# Volterra_Carriage_Board.net
KiCad netlist of a schematic drawn in EAGLE
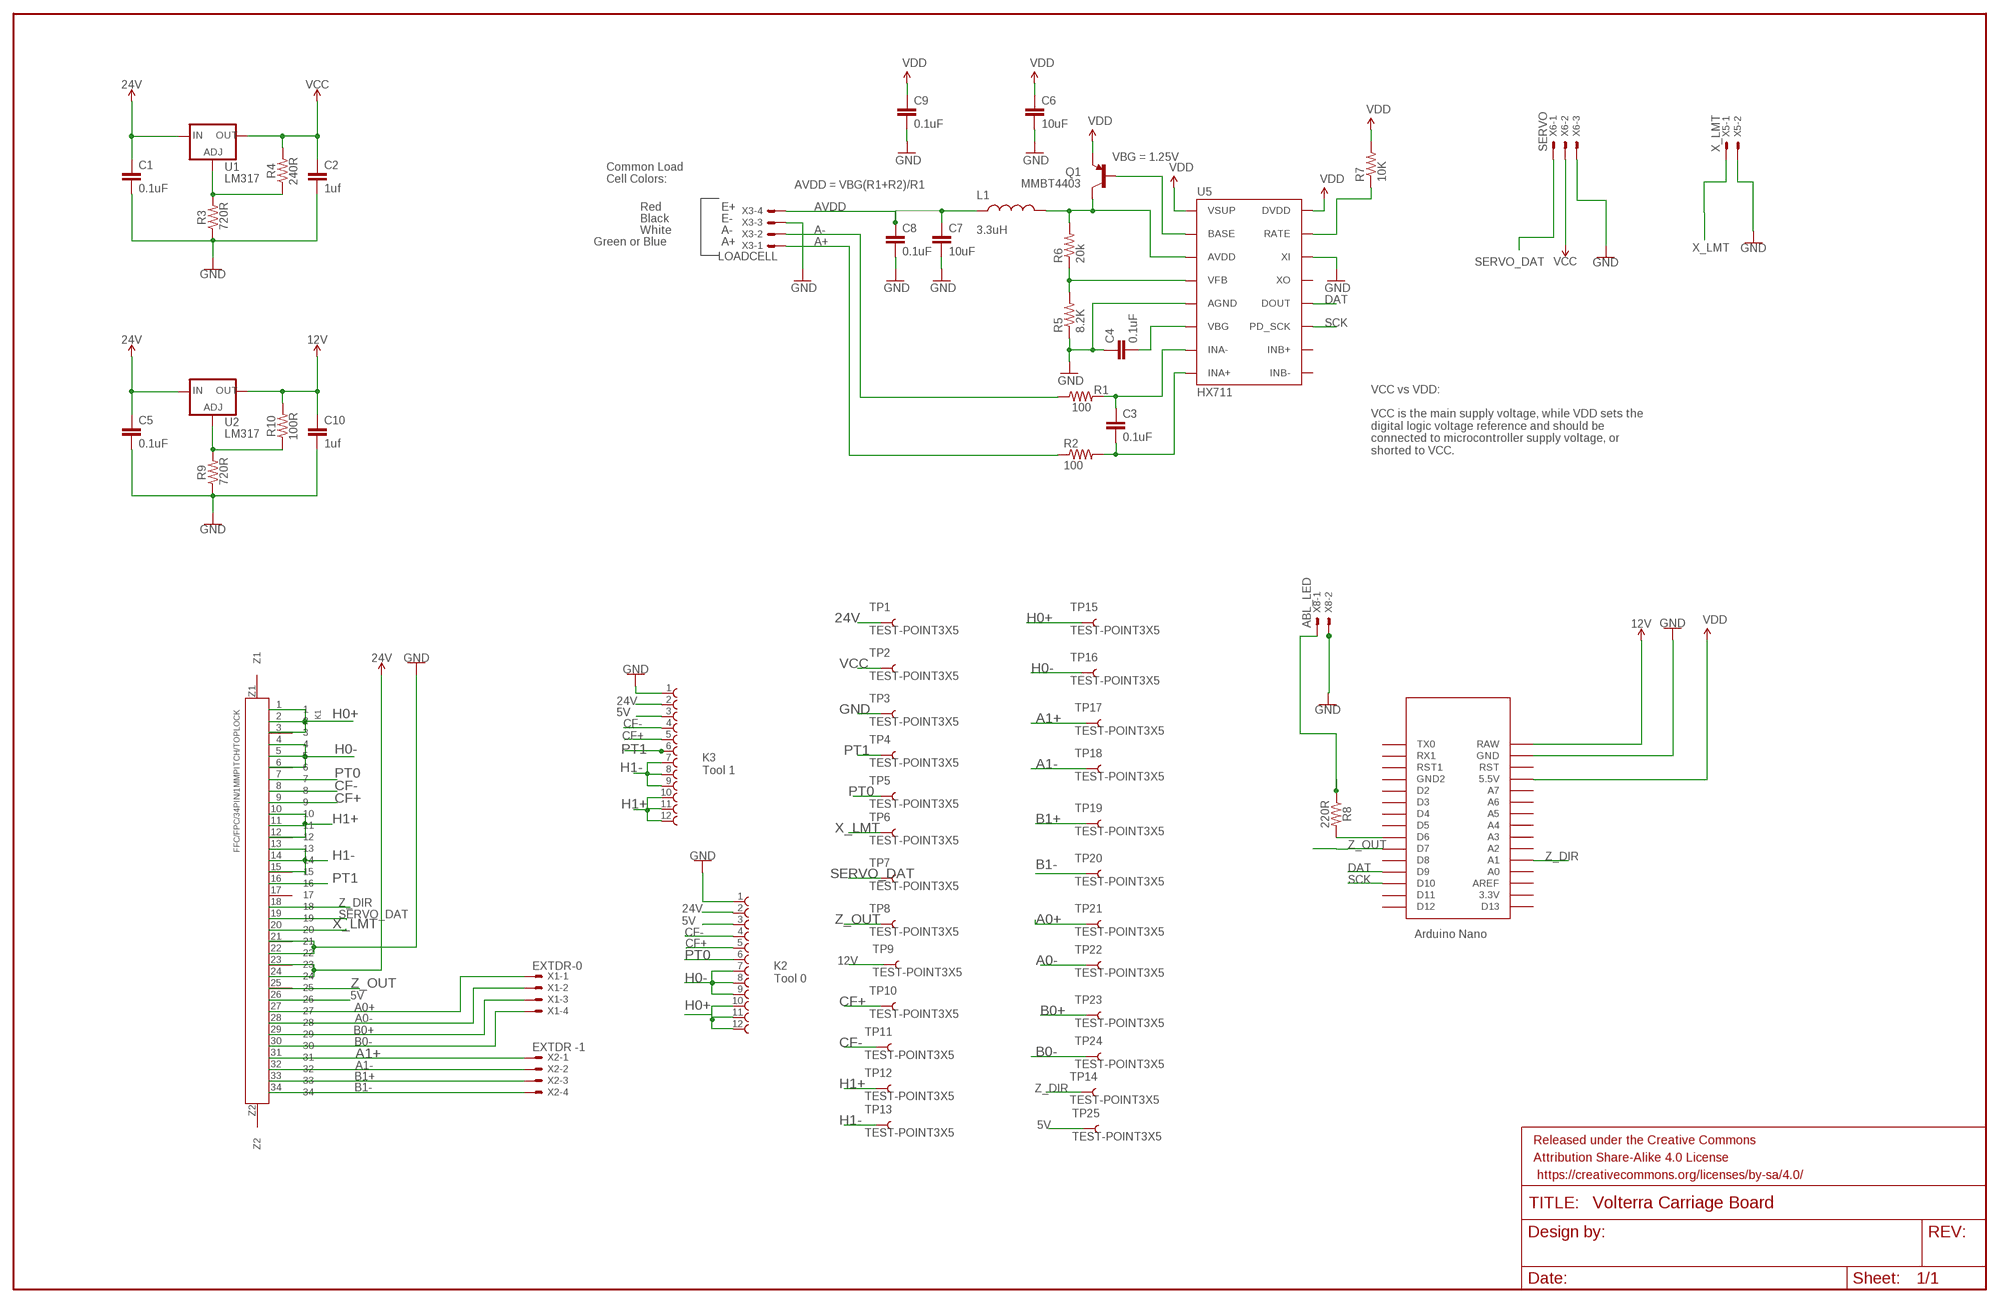
[diagram p0: schematic, sheet 1]

(export (version "E")
  (design (tool "Eeschema 10.0.6"))
  (components
    (comp (ref "C1")
      (value "0.1uF")
      (footprint "eagle-import:0603")
      (libsource (lib "eagle-import") (part "9.0PF-0603-50V-10%"))
    )
    (comp (ref "C2")
      (value "1uf")
      (footprint "eagle-import:0603")
      (libsource (lib "eagle-import") (part "9.0PF-0603-50V-10%"))
    )
    (comp (ref "C3")
      (value "0.1uF")
      (footprint "eagle-import:0603-CAP")
      (libsource (lib "eagle-import") (part "0.1UF-25V-5%(0603)"))
    )
    (comp (ref "C4")
      (value "0.1uF")
      (footprint "eagle-import:0603-CAP")
      (libsource (lib "eagle-import") (part "0.1UF-25V-5%(0603)"))
    )
    (comp (ref "C5")
      (value "0.1uF")
      (footprint "eagle-import:0603")
      (libsource (lib "eagle-import") (part "9.0PF-0603-50V-10%"))
    )
    (comp (ref "C6")
      (value "10uF")
      (footprint "eagle-import:1210")
      (libsource (lib "eagle-import") (part "10UF50V20%(1210)"))
    )
    (comp (ref "C7")
      (value "10uF")
      (footprint "eagle-import:1210")
      (libsource (lib "eagle-import") (part "10UF50V20%(1210)"))
    )
    (comp (ref "C8")
      (value "0.1uF")
      (footprint "eagle-import:0603-CAP")
      (libsource (lib "eagle-import") (part "0.1UF-25V-5%(0603)"))
    )
    (comp (ref "C9")
      (value "0.1uF")
      (footprint "eagle-import:0603-CAP")
      (libsource (lib "eagle-import") (part "0.1UF-25V-5%(0603)"))
    )
    (comp (ref "C10")
      (value "1uf")
      (footprint "eagle-import:0603")
      (libsource (lib "eagle-import") (part "9.0PF-0603-50V-10%"))
    )
    (comp (ref "FRAME1")
      (value "FRAME-LEDGER")
      (footprint "eagle-import:CREATIVE_COMMONS")
      (libsource (lib "eagle-import") (part "FRAME-LEDGER"))
    )
    (comp (ref "K1")
      (value "FFC/FPC/34PIN/1MMPITCH/TOPLOCK")
      (footprint "eagle-import:34PIN_1MMPITCH_FFC_FPC")
      (libsource (lib "eagle-import") (part "FFC/FPC/34PIN/1MMPITCH/TOPLOCK"))
    )
    (comp (ref "K2")
      (value "Tool 0")
      (footprint "eagle-import:68611214122")
      (libsource (lib "eagle-import") (part "68611214122"))
    )
    (comp (ref "K3")
      (value "Tool 1")
      (footprint "eagle-import:68611214122")
      (libsource (lib "eagle-import") (part "68611214122"))
    )
    (comp (ref "L1")
      (value "3.3uH")
      (footprint "eagle-import:0805")
      (libsource (lib "eagle-import") (part "INDUCTOR0805-IND"))
    )
    (comp (ref "Q1")
      (value "MMBT4403")
      (footprint "eagle-import:SOT23-3")
      (libsource (lib "eagle-import") (part "TRANSISTOR_PNPMMBT4403"))
    )
    (comp (ref "R1")
      (value "100")
      (footprint "eagle-import:0603-RES")
      (libsource (lib "eagle-import") (part "100OHM-1/10W-1%(0603)"))
    )
    (comp (ref "R2")
      (value "100")
      (footprint "eagle-import:0603-RES")
      (libsource (lib "eagle-import") (part "100OHM-1/10W-1%(0603)"))
    )
    (comp (ref "R3")
      (value "720R")
      (footprint "eagle-import:0603")
      (libsource (lib "eagle-import") (part "RESISTOR0603"))
    )
    (comp (ref "R4")
      (value "240R")
      (footprint "eagle-import:0603")
      (libsource (lib "eagle-import") (part "RESISTOR0603"))
    )
    (comp (ref "R5")
      (value "8.2K")
      (footprint "eagle-import:0603-RES")
      (libsource (lib "eagle-import") (part "8.2KOHM-1/10W-5%(0603)"))
    )
    (comp (ref "R6")
      (value "20k")
      (footprint "eagle-import:0603-RES")
      (libsource (lib "eagle-import") (part "20KOHM1/10W1%(0603)"))
    )
    (comp (ref "R7")
      (value "10K")
      (footprint "eagle-import:0603-RES")
      (libsource (lib "eagle-import") (part "10KOHM-1/10W-1%(0603)0603"))
    )
    (comp (ref "R8")
      (value "220R")
      (footprint "eagle-import:0603")
      (libsource (lib "eagle-import") (part "RESISTOR0603"))
    )
    (comp (ref "R9")
      (value "720R")
      (footprint "eagle-import:0603")
      (libsource (lib "eagle-import") (part "RESISTOR0603"))
    )
    (comp (ref "R10")
      (value "100R")
      (footprint "eagle-import:0603")
      (libsource (lib "eagle-import") (part "RESISTOR0603"))
    )
    (comp (ref "TP1")
      (value "TEST-POINT3X5")
      (footprint "eagle-import:PAD.03X.05")
      (libsource (lib "eagle-import") (part "TEST-POINT3X5"))
    )
    (comp (ref "TP2")
      (value "TEST-POINT3X5")
      (footprint "eagle-import:PAD.03X.05")
      (libsource (lib "eagle-import") (part "TEST-POINT3X5"))
    )
    (comp (ref "TP3")
      (value "TEST-POINT3X5")
      (footprint "eagle-import:PAD.03X.05")
      (libsource (lib "eagle-import") (part "TEST-POINT3X5"))
    )
    (comp (ref "TP4")
      (value "TEST-POINT3X5")
      (footprint "eagle-import:PAD.03X.05")
      (libsource (lib "eagle-import") (part "TEST-POINT3X5"))
    )
    (comp (ref "TP5")
      (value "TEST-POINT3X5")
      (footprint "eagle-import:PAD.03X.05")
      (libsource (lib "eagle-import") (part "TEST-POINT3X5"))
    )
    (comp (ref "TP6")
      (value "TEST-POINT3X5")
      (footprint "eagle-import:PAD.03X.05")
      (libsource (lib "eagle-import") (part "TEST-POINT3X5"))
    )
    (comp (ref "TP7")
      (value "TEST-POINT3X5")
      (footprint "eagle-import:PAD.03X.05")
      (libsource (lib "eagle-import") (part "TEST-POINT3X5"))
    )
    (comp (ref "TP8")
      (value "TEST-POINT3X5")
      (footprint "eagle-import:PAD.03X.05")
      (libsource (lib "eagle-import") (part "TEST-POINT3X5"))
    )
    (comp (ref "TP9")
      (value "TEST-POINT3X5")
      (footprint "eagle-import:PAD.03X.05")
      (libsource (lib "eagle-import") (part "TEST-POINT3X5"))
    )
    (comp (ref "TP10")
      (value "TEST-POINT3X5")
      (footprint "eagle-import:PAD.03X.05")
      (libsource (lib "eagle-import") (part "TEST-POINT3X5"))
    )
    (comp (ref "TP11")
      (value "TEST-POINT3X5")
      (footprint "eagle-import:PAD.03X.05")
      (libsource (lib "eagle-import") (part "TEST-POINT3X5"))
    )
    (comp (ref "TP12")
      (value "TEST-POINT3X5")
      (footprint "eagle-import:PAD.03X.05")
      (libsource (lib "eagle-import") (part "TEST-POINT3X5"))
    )
    (comp (ref "TP13")
      (value "TEST-POINT3X5")
      (footprint "eagle-import:PAD.03X.05")
      (libsource (lib "eagle-import") (part "TEST-POINT3X5"))
    )
    (comp (ref "TP14")
      (value "TEST-POINT3X5")
      (footprint "eagle-import:PAD.03X.05")
      (libsource (lib "eagle-import") (part "TEST-POINT3X5"))
    )
    (comp (ref "TP15")
      (value "TEST-POINT3X5")
      (footprint "eagle-import:PAD.03X.05")
      (libsource (lib "eagle-import") (part "TEST-POINT3X5"))
    )
    (comp (ref "TP16")
      (value "TEST-POINT3X5")
      (footprint "eagle-import:PAD.03X.05")
      (libsource (lib "eagle-import") (part "TEST-POINT3X5"))
    )
    (comp (ref "TP17")
      (value "TEST-POINT3X5")
      (footprint "eagle-import:PAD.03X.05")
      (libsource (lib "eagle-import") (part "TEST-POINT3X5"))
    )
    (comp (ref "TP18")
      (value "TEST-POINT3X5")
      (footprint "eagle-import:PAD.03X.05")
      (libsource (lib "eagle-import") (part "TEST-POINT3X5"))
    )
    (comp (ref "TP19")
      (value "TEST-POINT3X5")
      (footprint "eagle-import:PAD.03X.05")
      (libsource (lib "eagle-import") (part "TEST-POINT3X5"))
    )
    (comp (ref "TP20")
      (value "TEST-POINT3X5")
      (footprint "eagle-import:PAD.03X.05")
      (libsource (lib "eagle-import") (part "TEST-POINT3X5"))
    )
    (comp (ref "TP21")
      (value "TEST-POINT3X5")
      (footprint "eagle-import:PAD.03X.05")
      (libsource (lib "eagle-import") (part "TEST-POINT3X5"))
    )
    (comp (ref "TP22")
      (value "TEST-POINT3X5")
      (footprint "eagle-import:PAD.03X.05")
      (libsource (lib "eagle-import") (part "TEST-POINT3X5"))
    )
    (comp (ref "TP23")
      (value "TEST-POINT3X5")
      (footprint "eagle-import:PAD.03X.05")
      (libsource (lib "eagle-import") (part "TEST-POINT3X5"))
    )
    (comp (ref "TP24")
      (value "TEST-POINT3X5")
      (footprint "eagle-import:PAD.03X.05")
      (libsource (lib "eagle-import") (part "TEST-POINT3X5"))
    )
    (comp (ref "TP25")
      (value "TEST-POINT3X5")
      (footprint "eagle-import:PAD.03X.05")
      (libsource (lib "eagle-import") (part "TEST-POINT3X5"))
    )
    (comp (ref "U$1")
      (value "NANO")
      (footprint "eagle-import:NANO")
      (libsource (lib "eagle-import") (part "NANO"))
    )
    (comp (ref "U1")
      (value "LM317")
      (footprint "eagle-import:SOT223")
      (libsource (lib "eagle-import") (part "V_REG_317SMD"))
    )
    (comp (ref "U2")
      (value "LM317")
      (footprint "eagle-import:SOT223")
      (libsource (lib "eagle-import") (part "V_REG_317SMD"))
    )
    (comp (ref "U5")
      (value "HX711")
      (footprint "eagle-import:SO16")
      (libsource (lib "eagle-import") (part "HX711HX711"))
    )
    (comp (ref "X1")
      (value "EXTDR-0")
      (footprint "eagle-import:JST-XH-04-PACKAGE-LONG-PAD")
      (libsource (lib "eagle-import") (part "JST-XH-04-PIN-LONG-PAD"))
    )
    (comp (ref "X2")
      (value "EXTDR -1")
      (footprint "eagle-import:JST-XH-04-PACKAGE-LONG-PAD")
      (libsource (lib "eagle-import") (part "JST-XH-04-PIN-LONG-PAD"))
    )
    (comp (ref "X3")
      (value "LOADCELL")
      (footprint "eagle-import:JST-XH-04-PACKAGE-LONG-PAD")
      (libsource (lib "eagle-import") (part "JST-XH-04-PIN-LONG-PAD"))
    )
    (comp (ref "X5")
      (value "X_LMT")
      (footprint "eagle-import:JST-XH-02-PACKAGE-LONG-PAD")
      (libsource (lib "eagle-import") (part "JST-XH-02-PIN-LONG-PAD"))
    )
    (comp (ref "X6")
      (value "SERVO")
      (footprint "eagle-import:JST-XH-03-PACKAGE-LONG-PAD")
      (libsource (lib "eagle-import") (part "JST-XH-03-PIN-LONG-PAD"))
    )
    (comp (ref "X8")
      (value "ABL_LED")
      (footprint "eagle-import:JST-XH-02-PACKAGE-LONG-PAD")
      (libsource (lib "eagle-import") (part "JST-XH-02-PIN-LONG-PAD"))
    )
  )
  (nets
    (net (code "1") (name "/5V") (class "Default")
      (node (ref "K1") (pin "26") (pinfunction "26_26") (pintype "bidirectional"))
      (node (ref "K2") (pin "3") (pinfunction "3_3") (pintype "passive"))
      (node (ref "K3") (pin "3") (pinfunction "3_3") (pintype "passive"))
      (node (ref "TP25") (pin "P$1") (pinfunction "1_P$1") (pintype "bidirectional"))
    )
    (net (code "2") (name "/A+") (class "Default")
      (node (ref "R2") (pin "1") (pinfunction "1_1") (pintype "passive"))
      (node (ref "X3") (pin "1") (pinfunction "S_1") (pintype "passive"))
    )
    (net (code "3") (name "/A-") (class "Default")
      (node (ref "R1") (pin "1") (pinfunction "1_1") (pintype "passive"))
      (node (ref "X3") (pin "2") (pinfunction "S_2") (pintype "passive"))
    )
    (net (code "4") (name "/A0+") (class "Default")
      (node (ref "K1") (pin "27") (pinfunction "27_27") (pintype "bidirectional"))
      (node (ref "TP21") (pin "P$1") (pinfunction "1_P$1") (pintype "bidirectional"))
      (node (ref "X1") (pin "1") (pinfunction "S_1") (pintype "passive"))
    )
    (net (code "5") (name "/A0-") (class "Default")
      (node (ref "K1") (pin "28") (pinfunction "28_28") (pintype "bidirectional"))
      (node (ref "TP22") (pin "P$1") (pinfunction "1_P$1") (pintype "bidirectional"))
      (node (ref "X1") (pin "2") (pinfunction "S_2") (pintype "passive"))
    )
    (net (code "6") (name "/A1+") (class "Default")
      (node (ref "K1") (pin "31") (pinfunction "31_31") (pintype "bidirectional"))
      (node (ref "TP17") (pin "P$1") (pinfunction "1_P$1") (pintype "bidirectional"))
      (node (ref "X2") (pin "1") (pinfunction "S_1") (pintype "passive"))
    )
    (net (code "7") (name "/A1-") (class "Default")
      (node (ref "K1") (pin "32") (pinfunction "32_32") (pintype "bidirectional"))
      (node (ref "TP18") (pin "P$1") (pinfunction "1_P$1") (pintype "bidirectional"))
      (node (ref "X2") (pin "2") (pinfunction "S_2") (pintype "passive"))
    )
    (net (code "8") (name "/AVDD") (class "Default")
      (node (ref "C7") (pin "1") (pinfunction "1_1") (pintype "passive"))
      (node (ref "C8") (pin "1") (pinfunction "1_1") (pintype "passive"))
      (node (ref "L1") (pin "1") (pinfunction "1_1") (pintype "passive"))
      (node (ref "X3") (pin "4") (pinfunction "S_4") (pintype "passive"))
    )
    (net (code "9") (name "/B0+") (class "Default")
      (node (ref "K1") (pin "29") (pinfunction "29_29") (pintype "bidirectional"))
      (node (ref "TP23") (pin "P$1") (pinfunction "1_P$1") (pintype "bidirectional"))
      (node (ref "X1") (pin "3") (pinfunction "S_3") (pintype "passive"))
    )
    (net (code "10") (name "/B0-") (class "Default")
      (node (ref "K1") (pin "30") (pinfunction "30_30") (pintype "bidirectional"))
      (node (ref "TP24") (pin "P$1") (pinfunction "1_P$1") (pintype "bidirectional"))
      (node (ref "X1") (pin "4") (pinfunction "S_4") (pintype "passive"))
    )
    (net (code "11") (name "/B1+") (class "Default")
      (node (ref "K1") (pin "33") (pinfunction "33_33") (pintype "bidirectional"))
      (node (ref "TP19") (pin "P$1") (pinfunction "1_P$1") (pintype "bidirectional"))
      (node (ref "X2") (pin "3") (pinfunction "S_3") (pintype "passive"))
    )
    (net (code "12") (name "/B1-") (class "Default")
      (node (ref "K1") (pin "34") (pinfunction "34_34") (pintype "bidirectional"))
      (node (ref "TP20") (pin "P$1") (pinfunction "1_P$1") (pintype "bidirectional"))
      (node (ref "X2") (pin "4") (pinfunction "S_4") (pintype "passive"))
    )
    (net (code "13") (name "/CF+") (class "Default")
      (node (ref "K1") (pin "9") (pinfunction "9_9") (pintype "bidirectional"))
      (node (ref "K2") (pin "5") (pinfunction "5_5") (pintype "passive"))
      (node (ref "K3") (pin "5") (pinfunction "5_5") (pintype "passive"))
      (node (ref "TP10") (pin "P$1") (pinfunction "1_P$1") (pintype "bidirectional"))
    )
    (net (code "14") (name "/CF-") (class "Default")
      (node (ref "K1") (pin "8") (pinfunction "8_8") (pintype "bidirectional"))
      (node (ref "K2") (pin "4") (pinfunction "4_4") (pintype "passive"))
      (node (ref "K3") (pin "4") (pinfunction "4_4") (pintype "passive"))
      (node (ref "TP11") (pin "P$1") (pinfunction "1_P$1") (pintype "bidirectional"))
    )
    (net (code "15") (name "/DAT") (class "Default")
      (node (ref "U$1") (pin "D9") (pinfunction "D9_D9") (pintype "bidirectional"))
      (node (ref "U5") (pin "12") (pinfunction "DOUT_12") (pintype "bidirectional"))
    )
    (net (code "16") (name "/H0+") (class "Default")
      (node (ref "K1") (pin "1") (pinfunction "1_1") (pintype "bidirectional"))
      (node (ref "K1") (pin "2") (pinfunction "2_2") (pintype "bidirectional"))
      (node (ref "K1") (pin "3") (pinfunction "3_3") (pintype "bidirectional"))
      (node (ref "K2") (pin "10") (pinfunction "10_10") (pintype "passive"))
      (node (ref "K2") (pin "11") (pinfunction "11_11") (pintype "passive"))
      (node (ref "K2") (pin "12") (pinfunction "12_12") (pintype "passive"))
      (node (ref "TP15") (pin "P$1") (pinfunction "1_P$1") (pintype "bidirectional"))
    )
    (net (code "17") (name "/H0-") (class "Default")
      (node (ref "K1") (pin "4") (pinfunction "4_4") (pintype "bidirectional"))
      (node (ref "K1") (pin "5") (pinfunction "5_5") (pintype "bidirectional"))
      (node (ref "K1") (pin "6") (pinfunction "6_6") (pintype "bidirectional"))
      (node (ref "K2") (pin "7") (pinfunction "7_7") (pintype "passive"))
      (node (ref "K2") (pin "8") (pinfunction "8_8") (pintype "passive"))
      (node (ref "K2") (pin "9") (pinfunction "9_9") (pintype "passive"))
      (node (ref "TP16") (pin "P$1") (pinfunction "1_P$1") (pintype "bidirectional"))
    )
    (net (code "18") (name "/H1+") (class "Default")
      (node (ref "K1") (pin "10") (pinfunction "10_10") (pintype "bidirectional"))
      (node (ref "K1") (pin "11") (pinfunction "11_11") (pintype "bidirectional"))
      (node (ref "K1") (pin "12") (pinfunction "12_12") (pintype "bidirectional"))
      (node (ref "K3") (pin "10") (pinfunction "10_10") (pintype "passive"))
      (node (ref "K3") (pin "11") (pinfunction "11_11") (pintype "passive"))
      (node (ref "K3") (pin "12") (pinfunction "12_12") (pintype "passive"))
      (node (ref "TP12") (pin "P$1") (pinfunction "1_P$1") (pintype "bidirectional"))
    )
    (net (code "19") (name "/H1-") (class "Default")
      (node (ref "K1") (pin "13") (pinfunction "13_13") (pintype "bidirectional"))
      (node (ref "K1") (pin "14") (pinfunction "14_14") (pintype "bidirectional"))
      (node (ref "K1") (pin "15") (pinfunction "15_15") (pintype "bidirectional"))
      (node (ref "K3") (pin "7") (pinfunction "7_7") (pintype "passive"))
      (node (ref "K3") (pin "8") (pinfunction "8_8") (pintype "passive"))
      (node (ref "K3") (pin "9") (pinfunction "9_9") (pintype "passive"))
      (node (ref "TP13") (pin "P$1") (pinfunction "1_P$1") (pintype "bidirectional"))
    )
    (net (code "20") (name "/PT0") (class "Default")
      (node (ref "K1") (pin "7") (pinfunction "7_7") (pintype "bidirectional"))
      (node (ref "K2") (pin "6") (pinfunction "6_6") (pintype "passive"))
      (node (ref "TP5") (pin "P$1") (pinfunction "1_P$1") (pintype "bidirectional"))
    )
    (net (code "21") (name "/PT1") (class "Default")
      (node (ref "K1") (pin "16") (pinfunction "16_16") (pintype "bidirectional"))
      (node (ref "K3") (pin "6") (pinfunction "6_6") (pintype "passive"))
      (node (ref "TP4") (pin "P$1") (pinfunction "1_P$1") (pintype "bidirectional"))
    )
    (net (code "22") (name "/SCK") (class "Default")
      (node (ref "U$1") (pin "D10") (pinfunction "D10_D10") (pintype "bidirectional"))
      (node (ref "U5") (pin "11") (pinfunction "PD_SCK_11") (pintype "bidirectional"))
    )
    (net (code "23") (name "/SERVO_DAT") (class "Default")
      (node (ref "K1") (pin "19") (pinfunction "19_19") (pintype "bidirectional"))
      (node (ref "TP7") (pin "P$1") (pinfunction "1_P$1") (pintype "bidirectional"))
      (node (ref "X6") (pin "1") (pinfunction "S_1") (pintype "passive"))
    )
    (net (code "24") (name "/X_LMT") (class "Default")
      (node (ref "K1") (pin "20") (pinfunction "20_20") (pintype "bidirectional"))
      (node (ref "TP6") (pin "P$1") (pinfunction "1_P$1") (pintype "bidirectional"))
      (node (ref "X5") (pin "1") (pinfunction "S_1") (pintype "passive"))
    )
    (net (code "25") (name "/Z_DIR") (class "Default")
      (node (ref "K1") (pin "18") (pinfunction "18_18") (pintype "bidirectional"))
      (node (ref "TP14") (pin "P$1") (pinfunction "1_P$1") (pintype "bidirectional"))
      (node (ref "U$1") (pin "A1") (pinfunction "A1_A1") (pintype "bidirectional"))
    )
    (net (code "26") (name "/Z_OUT") (class "Default")
      (node (ref "K1") (pin "25") (pinfunction "25_25") (pintype "bidirectional"))
      (node (ref "TP8") (pin "P$1") (pinfunction "1_P$1") (pintype "bidirectional"))
      (node (ref "U$1") (pin "D7") (pinfunction "D7_D7") (pintype "bidirectional"))
    )
    (net (code "27") (name "12V") (class "Default")
      (node (ref "C10") (pin "1") (pinfunction "1_1") (pintype "passive"))
      (node (ref "R10") (pin "2") (pinfunction "2_2") (pintype "passive"))
      (node (ref "TP9") (pin "P$1") (pinfunction "1_P$1") (pintype "bidirectional"))
      (node (ref "U$1") (pin "RAW") (pinfunction "RAW_RAW") (pintype "bidirectional"))
      (node (ref "U2") (pin "2") (pinfunction "OUT_2") (pintype "output"))
    )
    (net (code "28") (name "24V") (class "Default")
      (node (ref "C1") (pin "1") (pinfunction "1_1") (pintype "passive"))
      (node (ref "C5") (pin "1") (pinfunction "1_1") (pintype "passive"))
      (node (ref "K1") (pin "23") (pinfunction "23_23") (pintype "bidirectional"))
      (node (ref "K1") (pin "24") (pinfunction "24_24") (pintype "bidirectional"))
      (node (ref "K2") (pin "2") (pinfunction "2_2") (pintype "passive"))
      (node (ref "K3") (pin "2") (pinfunction "2_2") (pintype "passive"))
      (node (ref "TP1") (pin "P$1") (pinfunction "1_P$1") (pintype "bidirectional"))
      (node (ref "U1") (pin "3") (pinfunction "IN_3") (pintype "input"))
      (node (ref "U2") (pin "3") (pinfunction "IN_3") (pintype "input"))
    )
    (net (code "29") (name "GND") (class "Default")
      (node (ref "C1") (pin "2") (pinfunction "2_2") (pintype "passive"))
      (node (ref "C10") (pin "2") (pinfunction "2_2") (pintype "passive"))
      (node (ref "C2") (pin "2") (pinfunction "2_2") (pintype "passive"))
      (node (ref "C4") (pin "1") (pinfunction "1_1") (pintype "passive"))
      (node (ref "C5") (pin "2") (pinfunction "2_2") (pintype "passive"))
      (node (ref "C6") (pin "2") (pinfunction "2_2") (pintype "passive"))
      (node (ref "C7") (pin "2") (pinfunction "2_2") (pintype "passive"))
      (node (ref "C8") (pin "2") (pinfunction "2_2") (pintype "passive"))
      (node (ref "C9") (pin "2") (pinfunction "2_2") (pintype "passive"))
      (node (ref "K1") (pin "21") (pinfunction "21_21") (pintype "bidirectional"))
      (node (ref "K1") (pin "22") (pinfunction "22_22") (pintype "bidirectional"))
      (node (ref "K2") (pin "1") (pinfunction "1_1") (pintype "passive"))
      (node (ref "K3") (pin "1") (pinfunction "1_1") (pintype "passive"))
      (node (ref "R3") (pin "1") (pinfunction "1_1") (pintype "passive"))
      (node (ref "R5") (pin "1") (pinfunction "1_1") (pintype "passive"))
      (node (ref "R9") (pin "1") (pinfunction "1_1") (pintype "passive"))
      (node (ref "TP3") (pin "P$1") (pinfunction "1_P$1") (pintype "bidirectional"))
      (node (ref "U$1") (pin "GND") (pinfunction "GND_GND") (pintype "bidirectional"))
      (node (ref "U5") (pin "14") (pinfunction "XI_14") (pintype "bidirectional"))
      (node (ref "U5") (pin "5") (pinfunction "AGND_5") (pintype "bidirectional"))
      (node (ref "X3") (pin "3") (pinfunction "S_3") (pintype "passive"))
      (node (ref "X5") (pin "2") (pinfunction "S_2") (pintype "passive"))
      (node (ref "X6") (pin "3") (pinfunction "S_3") (pintype "passive"))
      (node (ref "X8") (pin "2") (pinfunction "S_2") (pintype "passive"))
    )
    (net (code "30") (name "Net-(Q1-B)") (class "Default")
      (node (ref "Q1") (pin "1") (pinfunction "B_1") (pintype "passive"))
      (node (ref "U5") (pin "2") (pinfunction "BASE_2") (pintype "bidirectional"))
    )
    (net (code "31") (name "Net-(Q1-C)") (class "Default")
      (node (ref "L1") (pin "2") (pinfunction "2_2") (pintype "passive"))
      (node (ref "Q1") (pin "3") (pinfunction "C_3") (pintype "passive"))
      (node (ref "R6") (pin "2") (pinfunction "2_2") (pintype "passive"))
      (node (ref "U5") (pin "3") (pinfunction "AVDD_3") (pintype "bidirectional"))
    )
    (net (code "32") (name "Net-(R8-Pad2)") (class "Default")
      (node (ref "R8") (pin "2") (pinfunction "2_2") (pintype "passive"))
      (node (ref "U$1") (pin "D6") (pinfunction "D6_D6") (pintype "bidirectional"))
    )
    (net (code "33") (name "Net-(U1-ADJ)") (class "Default")
      (node (ref "R3") (pin "2") (pinfunction "2_2") (pintype "passive"))
      (node (ref "R4") (pin "1") (pinfunction "1_1") (pintype "passive"))
      (node (ref "U1") (pin "1") (pinfunction "ADJ_1") (pintype "input"))
    )
    (net (code "34") (name "Net-(U2-ADJ)") (class "Default")
      (node (ref "R10") (pin "1") (pinfunction "1_1") (pintype "passive"))
      (node (ref "R9") (pin "2") (pinfunction "2_2") (pintype "passive"))
      (node (ref "U2") (pin "1") (pinfunction "ADJ_1") (pintype "input"))
    )
    (net (code "35") (name "Net-(U5-INA+)") (class "Default")
      (node (ref "C3") (pin "2") (pinfunction "2_2") (pintype "passive"))
      (node (ref "R2") (pin "2") (pinfunction "2_2") (pintype "passive"))
      (node (ref "U5") (pin "8") (pinfunction "INA+_8") (pintype "bidirectional"))
    )
    (net (code "36") (name "Net-(U5-INA-)") (class "Default")
      (node (ref "C3") (pin "1") (pinfunction "1_1") (pintype "passive"))
      (node (ref "R1") (pin "2") (pinfunction "2_2") (pintype "passive"))
      (node (ref "U5") (pin "7") (pinfunction "INA-_7") (pintype "bidirectional"))
    )
    (net (code "37") (name "Net-(U5-RATE)") (class "Default")
      (node (ref "R7") (pin "1") (pinfunction "1_1") (pintype "passive"))
      (node (ref "U5") (pin "15") (pinfunction "RATE_15") (pintype "bidirectional"))
    )
    (net (code "38") (name "Net-(U5-VBG)") (class "Default")
      (node (ref "C4") (pin "2") (pinfunction "2_2") (pintype "passive"))
      (node (ref "U5") (pin "6") (pinfunction "VBG_6") (pintype "bidirectional"))
    )
    (net (code "39") (name "Net-(U5-VFB)") (class "Default")
      (node (ref "R5") (pin "2") (pinfunction "2_2") (pintype "passive"))
      (node (ref "R6") (pin "1") (pinfunction "1_1") (pintype "passive"))
      (node (ref "U5") (pin "4") (pinfunction "VFB_4") (pintype "bidirectional"))
    )
    (net (code "40") (name "Net-(X8A-S)") (class "Default")
      (node (ref "R8") (pin "1") (pinfunction "1_1") (pintype "passive"))
      (node (ref "X8") (pin "1") (pinfunction "S_1") (pintype "passive"))
    )
    (net (code "41") (name "VCC") (class "Default")
      (node (ref "C2") (pin "1") (pinfunction "1_1") (pintype "passive"))
      (node (ref "R4") (pin "2") (pinfunction "2_2") (pintype "passive"))
      (node (ref "TP2") (pin "P$1") (pinfunction "1_P$1") (pintype "bidirectional"))
      (node (ref "U1") (pin "2") (pinfunction "OUT_2") (pintype "output"))
      (node (ref "X6") (pin "2") (pinfunction "S_2") (pintype "passive"))
    )
    (net (code "42") (name "VDD") (class "Default")
      (node (ref "C6") (pin "1") (pinfunction "1_1") (pintype "passive"))
      (node (ref "C9") (pin "1") (pinfunction "1_1") (pintype "passive"))
      (node (ref "Q1") (pin "2") (pinfunction "E_2") (pintype "passive"))
      (node (ref "R7") (pin "2") (pinfunction "2_2") (pintype "passive"))
      (node (ref "U$1") (pin "5V") (pinfunction "5.5V_5V") (pintype "bidirectional"))
      (node (ref "U5") (pin "1") (pinfunction "VSUP_1") (pintype "bidirectional"))
      (node (ref "U5") (pin "16") (pinfunction "DVDD_16") (pintype "bidirectional"))
    )
    (net (code "43") (name "unconnected-(K1-Pad17)") (class "Default")
      (node (ref "K1") (pin "17") (pinfunction "17_17") (pintype "bidirectional"))
    )
    (net (code "44") (name "unconnected-(K1-PadZ1)") (class "Default")
      (node (ref "K1") (pin "Z1") (pinfunction "Z1_Z1") (pintype "bidirectional"))
    )
    (net (code "45") (name "unconnected-(K1-PadZ2)") (class "Default")
      (node (ref "K1") (pin "Z2") (pinfunction "Z2_Z2") (pintype "bidirectional"))
    )
    (net (code "46") (name "unconnected-(U$1-GND2-PadGND1)") (class "Default")
      (node (ref "U$1") (pin "GND1") (pinfunction "GND2_GND1") (pintype "bidirectional"))
    )
    (net (code "47") (name "unconnected-(U$1-Pad3.3V)") (class "Default")
      (node (ref "U$1") (pin "3.3V") (pinfunction "3.3V_3.3V") (pintype "bidirectional"))
    )
    (net (code "48") (name "unconnected-(U$1-PadA0)") (class "Default")
      (node (ref "U$1") (pin "A0") (pinfunction "A0_A0") (pintype "bidirectional"))
    )
    (net (code "49") (name "unconnected-(U$1-PadA2)") (class "Default")
      (node (ref "U$1") (pin "A2") (pinfunction "A2_A2") (pintype "bidirectional"))
    )
    (net (code "50") (name "unconnected-(U$1-PadA3)") (class "Default")
      (node (ref "U$1") (pin "A3") (pinfunction "A3_A3") (pintype "bidirectional"))
    )
    (net (code "51") (name "unconnected-(U$1-PadA4)") (class "Default")
      (node (ref "U$1") (pin "A4") (pinfunction "A4_A4") (pintype "bidirectional"))
    )
    (net (code "52") (name "unconnected-(U$1-PadA5)") (class "Default")
      (node (ref "U$1") (pin "A5") (pinfunction "A5_A5") (pintype "bidirectional"))
    )
    (net (code "53") (name "unconnected-(U$1-PadA6)") (class "Default")
      (node (ref "U$1") (pin "A6") (pinfunction "A6_A6") (pintype "bidirectional"))
    )
    (net (code "54") (name "unconnected-(U$1-PadA7)") (class "Default")
      (node (ref "U$1") (pin "A7") (pinfunction "A7_A7") (pintype "bidirectional"))
    )
    (net (code "55") (name "unconnected-(U$1-PadAREF)") (class "Default")
      (node (ref "U$1") (pin "AREF") (pinfunction "AREF_AREF") (pintype "bidirectional"))
    )
    (net (code "56") (name "unconnected-(U$1-PadD2)") (class "Default")
      (node (ref "U$1") (pin "D2") (pinfunction "D2_D2") (pintype "bidirectional"))
    )
    (net (code "57") (name "unconnected-(U$1-PadD3)") (class "Default")
      (node (ref "U$1") (pin "D3") (pinfunction "D3_D3") (pintype "bidirectional"))
    )
    (net (code "58") (name "unconnected-(U$1-PadD4)") (class "Default")
      (node (ref "U$1") (pin "D4") (pinfunction "D4_D4") (pintype "bidirectional"))
    )
    (net (code "59") (name "unconnected-(U$1-PadD5)") (class "Default")
      (node (ref "U$1") (pin "D5") (pinfunction "D5_D5") (pintype "bidirectional"))
    )
    (net (code "60") (name "unconnected-(U$1-PadD8)") (class "Default")
      (node (ref "U$1") (pin "D8") (pinfunction "D8_D8") (pintype "bidirectional"))
    )
    (net (code "61") (name "unconnected-(U$1-PadD11)") (class "Default")
      (node (ref "U$1") (pin "D11") (pinfunction "D11_D11") (pintype "bidirectional"))
    )
    (net (code "62") (name "unconnected-(U$1-PadD12)") (class "Default")
      (node (ref "U$1") (pin "D12") (pinfunction "D12_D12") (pintype "bidirectional"))
    )
    (net (code "63") (name "unconnected-(U$1-PadD13)") (class "Default")
      (node (ref "U$1") (pin "D13") (pinfunction "D13_D13") (pintype "bidirectional"))
    )
    (net (code "64") (name "unconnected-(U$1-PadICSP1)") (class "Default")
      (node (ref "U$1") (pin "ICSP1") (pinfunction "ICSP1_ICSP1") (pintype "bidirectional"))
    )
    (net (code "65") (name "unconnected-(U$1-PadICSP2)") (class "Default")
      (node (ref "U$1") (pin "ICSP2") (pinfunction "ICSP2_ICSP2") (pintype "bidirectional"))
    )
    (net (code "66") (name "unconnected-(U$1-PadICSP3)") (class "Default")
      (node (ref "U$1") (pin "ICSP3") (pinfunction "ICSP3_ICSP3") (pintype "bidirectional"))
    )
    (net (code "67") (name "unconnected-(U$1-PadICSP4)") (class "Default")
      (node (ref "U$1") (pin "ICSP4") (pinfunction "ICSP4_ICSP4") (pintype "bidirectional"))
    )
    (net (code "68") (name "unconnected-(U$1-PadICSP5)") (class "Default")
      (node (ref "U$1") (pin "ICSP5") (pinfunction "ICSP5_ICSP5") (pintype "bidirectional"))
    )
    (net (code "69") (name "unconnected-(U$1-PadICSP6)") (class "Default")
      (node (ref "U$1") (pin "ICSP6") (pinfunction "ICSP6_ICSP6") (pintype "bidirectional"))
    )
    (net (code "70") (name "unconnected-(U$1-PadRST)") (class "Default")
      (node (ref "U$1") (pin "RST") (pinfunction "RST_RST") (pintype "bidirectional"))
    )
    (net (code "71") (name "unconnected-(U$1-PadRST1)") (class "Default")
      (node (ref "U$1") (pin "RST1") (pinfunction "RST1_RST1") (pintype "bidirectional"))
    )
    (net (code "72") (name "unconnected-(U$1-PadRX1)") (class "Default")
      (node (ref "U$1") (pin "RX1") (pinfunction "RX1_RX1") (pintype "bidirectional"))
    )
    (net (code "73") (name "unconnected-(U$1-PadTX0)") (class "Default")
      (node (ref "U$1") (pin "TX0") (pinfunction "TX0_TX0") (pintype "bidirectional"))
    )
    (net (code "74") (name "unconnected-(U5-INB+-Pad10)") (class "Default")
      (node (ref "U5") (pin "10") (pinfunction "INB+_10") (pintype "bidirectional"))
    )
    (net (code "75") (name "unconnected-(U5-INB--Pad9)") (class "Default")
      (node (ref "U5") (pin "9") (pinfunction "INB-_9") (pintype "bidirectional"))
    )
    (net (code "76") (name "unconnected-(U5-XO-Pad13)") (class "Default")
      (node (ref "U5") (pin "13") (pinfunction "XO_13") (pintype "bidirectional"))
    )
  )
)
